# board_exborgs_baru.net
KiCad netlist of a schematic drawn in EAGLE
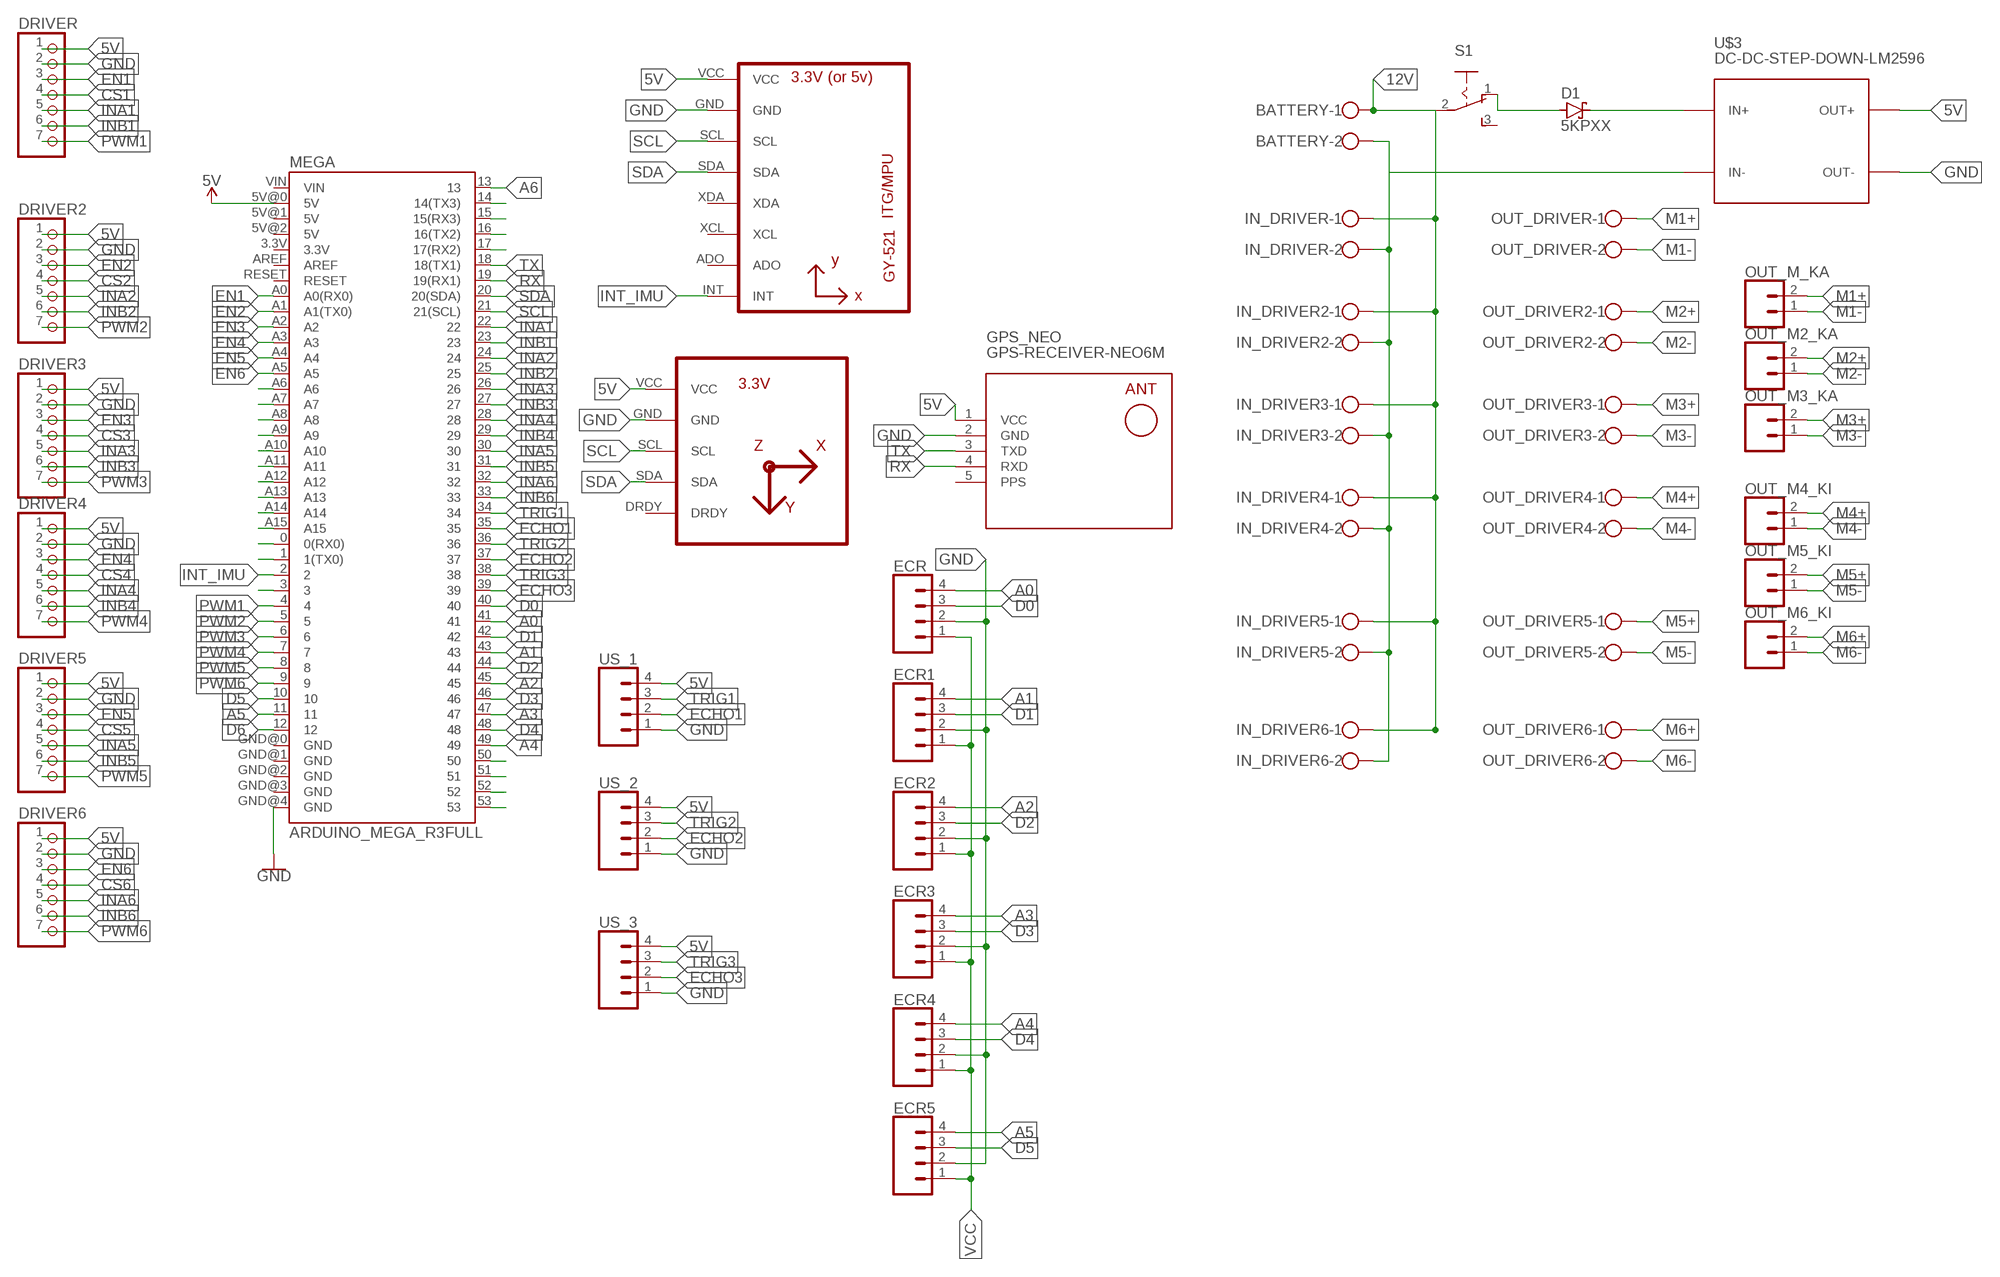
[diagram p0: schematic, sheet 1]

(export (version "E")
  (design (tool "Eeschema 10.0.6"))
  (components
    (comp (ref "BATTERY")
      (value "W237-102")
      (footprint "eagle-import:W237-102")
      (fields (field (name "MPN") "237-102"))
      (libsource (lib "eagle-import") (part "W237-102"))
    )
    (comp (ref "D1")
      (value "5KPXX")
      (footprint "eagle-import:P6T15")
      (libsource (lib "eagle-import") (part "5KPXX"))
    )
    (comp (ref "DRIVER")
      (value "PINHD-1X7")
      (footprint "eagle-import:1X07")
      (libsource (lib "eagle-import") (part "PINHD-1X7"))
    )
    (comp (ref "DRIVER2")
      (value "PINHD-1X7")
      (footprint "eagle-import:1X07")
      (libsource (lib "eagle-import") (part "PINHD-1X7"))
    )
    (comp (ref "DRIVER3")
      (value "PINHD-1X7")
      (footprint "eagle-import:1X07")
      (libsource (lib "eagle-import") (part "PINHD-1X7"))
    )
    (comp (ref "DRIVER4")
      (value "PINHD-1X7")
      (footprint "eagle-import:1X07")
      (libsource (lib "eagle-import") (part "PINHD-1X7"))
    )
    (comp (ref "DRIVER5")
      (value "PINHD-1X7")
      (footprint "eagle-import:1X07")
      (libsource (lib "eagle-import") (part "PINHD-1X7"))
    )
    (comp (ref "DRIVER6")
      (value "PINHD-1X7")
      (footprint "eagle-import:1X07")
      (libsource (lib "eagle-import") (part "PINHD-1X7"))
    )
    (comp (ref "ECR")
      (value "CONN_04POLAR")
      (footprint "eagle-import:MOLEX-1X4")
      (libsource (lib "eagle-import") (part "CONN_04POLAR"))
    )
    (comp (ref "ECR1")
      (value "CONN_04POLAR")
      (footprint "eagle-import:MOLEX-1X4")
      (libsource (lib "eagle-import") (part "CONN_04POLAR"))
    )
    (comp (ref "ECR2")
      (value "CONN_04POLAR")
      (footprint "eagle-import:MOLEX-1X4")
      (libsource (lib "eagle-import") (part "CONN_04POLAR"))
    )
    (comp (ref "ECR3")
      (value "CONN_04POLAR")
      (footprint "eagle-import:MOLEX-1X4")
      (libsource (lib "eagle-import") (part "CONN_04POLAR"))
    )
    (comp (ref "ECR4")
      (value "CONN_04POLAR")
      (footprint "eagle-import:MOLEX-1X4")
      (libsource (lib "eagle-import") (part "CONN_04POLAR"))
    )
    (comp (ref "ECR5")
      (value "CONN_04POLAR")
      (footprint "eagle-import:MOLEX-1X4")
      (libsource (lib "eagle-import") (part "CONN_04POLAR"))
    )
    (comp (ref "GPS_NEO")
      (value "GPS-RECEIVER-NEO6M")
      (footprint "eagle-import:GPS-RECEIVER-NEO6M")
      (libsource (lib "eagle-import") (part "GPS-RECEIVER-NEO6M"))
    )
    (comp (ref "IMU")
      (value "GY-521MPU6050")
      (footprint "eagle-import:GY-521")
      (libsource (lib "eagle-import") (part "GY-521MPU6050"))
    )
    (comp (ref "IN_DRIVER")
      (value "W237-102")
      (footprint "eagle-import:W237-102")
      (fields (field (name "MPN") "237-102"))
      (libsource (lib "eagle-import") (part "W237-102"))
    )
    (comp (ref "IN_DRIVER2")
      (value "W237-102")
      (footprint "eagle-import:W237-102")
      (fields (field (name "MPN") "237-102"))
      (libsource (lib "eagle-import") (part "W237-102"))
    )
    (comp (ref "IN_DRIVER3")
      (value "W237-102")
      (footprint "eagle-import:W237-102")
      (fields (field (name "MPN") "237-102"))
      (libsource (lib "eagle-import") (part "W237-102"))
    )
    (comp (ref "IN_DRIVER4")
      (value "W237-102")
      (footprint "eagle-import:W237-102")
      (fields (field (name "MPN") "237-102"))
      (libsource (lib "eagle-import") (part "W237-102"))
    )
    (comp (ref "IN_DRIVER5")
      (value "W237-102")
      (footprint "eagle-import:W237-102")
      (fields (field (name "MPN") "237-102"))
      (libsource (lib "eagle-import") (part "W237-102"))
    )
    (comp (ref "IN_DRIVER6")
      (value "W237-102")
      (footprint "eagle-import:W237-102")
      (fields (field (name "MPN") "237-102"))
      (libsource (lib "eagle-import") (part "W237-102"))
    )
    (comp (ref "KOMPAS")
      (value "HMC5883LGY-271")
      (footprint "eagle-import:GY-271")
      (libsource (lib "eagle-import") (part "HMC5883LGY-271"))
    )
    (comp (ref "MEGA")
      (value "ARDUINO_MEGA_R3FULL")
      (footprint "eagle-import:ARDUINO_MEGA")
      (libsource (lib "eagle-import") (part "ARDUINO_MEGA_R3FULL"))
    )
    (comp (ref "OUT_DRIVER")
      (value "W237-102")
      (footprint "eagle-import:W237-102")
      (fields (field (name "MPN") "237-102"))
      (libsource (lib "eagle-import") (part "W237-102"))
    )
    (comp (ref "OUT_DRIVER2")
      (value "W237-102")
      (footprint "eagle-import:W237-102")
      (fields (field (name "MPN") "237-102"))
      (libsource (lib "eagle-import") (part "W237-102"))
    )
    (comp (ref "OUT_DRIVER3")
      (value "W237-102")
      (footprint "eagle-import:W237-102")
      (fields (field (name "MPN") "237-102"))
      (libsource (lib "eagle-import") (part "W237-102"))
    )
    (comp (ref "OUT_DRIVER4")
      (value "W237-102")
      (footprint "eagle-import:W237-102")
      (fields (field (name "MPN") "237-102"))
      (libsource (lib "eagle-import") (part "W237-102"))
    )
    (comp (ref "OUT_DRIVER5")
      (value "W237-102")
      (footprint "eagle-import:W237-102")
      (fields (field (name "MPN") "237-102"))
      (libsource (lib "eagle-import") (part "W237-102"))
    )
    (comp (ref "OUT_DRIVER6")
      (value "W237-102")
      (footprint "eagle-import:W237-102")
      (fields (field (name "MPN") "237-102"))
      (libsource (lib "eagle-import") (part "W237-102"))
    )
    (comp (ref "OUT_M2_KA")
      (value "CONN_02POLAR")
      (footprint "eagle-import:MOLEX-1X2")
      (libsource (lib "eagle-import") (part "CONN_02POLAR"))
    )
    (comp (ref "OUT_M3_KA")
      (value "CONN_02POLAR")
      (footprint "eagle-import:MOLEX-1X2")
      (libsource (lib "eagle-import") (part "CONN_02POLAR"))
    )
    (comp (ref "OUT_M4_KI")
      (value "CONN_02POLAR")
      (footprint "eagle-import:MOLEX-1X2")
      (libsource (lib "eagle-import") (part "CONN_02POLAR"))
    )
    (comp (ref "OUT_M5_KI")
      (value "CONN_02POLAR")
      (footprint "eagle-import:MOLEX-1X2")
      (libsource (lib "eagle-import") (part "CONN_02POLAR"))
    )
    (comp (ref "OUT_M6_KI")
      (value "CONN_02POLAR")
      (footprint "eagle-import:MOLEX-1X2")
      (libsource (lib "eagle-import") (part "CONN_02POLAR"))
    )
    (comp (ref "OUT_M_KA")
      (value "CONN_02POLAR")
      (footprint "eagle-import:MOLEX-1X2")
      (libsource (lib "eagle-import") (part "CONN_02POLAR"))
    )
    (comp (ref "S1")
      (value "255SB")
      (footprint "eagle-import:255SB")
      (libsource (lib "eagle-import") (part "255SB"))
    )
    (comp (ref "U$3")
      (value "DC-DC-STEP-DOWN-LM2596")
      (footprint "eagle-import:DC-DC-STEP-DOWN-LM2596")
      (libsource (lib "eagle-import") (part "DC-DC-STEP-DOWN-LM2596"))
    )
    (comp (ref "US_1")
      (value "CONN_04POLAR")
      (footprint "eagle-import:MOLEX-1X4")
      (libsource (lib "eagle-import") (part "CONN_04POLAR"))
    )
    (comp (ref "US_2")
      (value "CONN_04POLAR")
      (footprint "eagle-import:MOLEX-1X4")
      (libsource (lib "eagle-import") (part "CONN_04POLAR"))
    )
    (comp (ref "US_3")
      (value "CONN_04POLAR")
      (footprint "eagle-import:MOLEX-1X4")
      (libsource (lib "eagle-import") (part "CONN_04POLAR"))
    )
  )
  (nets
    (net (code "1") (name "/PPS") (class "Default")
      (node (ref "GPS_NEO") (pin "5") (pinfunction "PPS_5") (pintype "power_in"))
    )
    (net (code "2") (name "5V") (class "Default")
      (node (ref "DRIVER") (pin "1") (pinfunction "1_1") (pintype "passive"))
      (node (ref "DRIVER2") (pin "1") (pinfunction "1_1") (pintype "passive"))
      (node (ref "DRIVER3") (pin "1") (pinfunction "1_1") (pintype "passive"))
      (node (ref "DRIVER4") (pin "1") (pinfunction "1_1") (pintype "passive"))
      (node (ref "DRIVER5") (pin "1") (pinfunction "1_1") (pintype "passive"))
      (node (ref "DRIVER6") (pin "1") (pinfunction "1_1") (pintype "passive"))
      (node (ref "GPS_NEO") (pin "1") (pinfunction "VCC_1") (pintype "bidirectional"))
      (node (ref "IMU") (pin "VCC") (pinfunction "VCC_VCC") (pintype "bidirectional"))
      (node (ref "KOMPAS") (pin "VCC") (pinfunction "VCC_VCC") (pintype "bidirectional"))
      (node (ref "MEGA") (pin "5V@0") (pinfunction "5V_5V@0") (pintype "bidirectional"))
      (node (ref "U$3") (pin "OUT+") (pinfunction "OUT+_OUT+") (pintype "bidirectional"))
      (node (ref "US_1") (pin "4") (pinfunction "4_4") (pintype "passive"))
      (node (ref "US_2") (pin "4") (pinfunction "4_4") (pintype "passive"))
      (node (ref "US_3") (pin "4") (pinfunction "4_4") (pintype "passive"))
    )
    (net (code "3") (name "12V") (class "Default")
      (node (ref "BATTERY") (pin "1") (pinfunction "KL_1") (pintype "passive"))
      (node (ref "IN_DRIVER") (pin "1") (pinfunction "KL_1") (pintype "passive"))
      (node (ref "IN_DRIVER2") (pin "1") (pinfunction "KL_1") (pintype "passive"))
      (node (ref "IN_DRIVER3") (pin "1") (pinfunction "KL_1") (pintype "passive"))
      (node (ref "IN_DRIVER4") (pin "1") (pinfunction "KL_1") (pintype "passive"))
      (node (ref "IN_DRIVER5") (pin "1") (pinfunction "KL_1") (pintype "passive"))
      (node (ref "IN_DRIVER6") (pin "1") (pinfunction "KL_1") (pintype "passive"))
      (node (ref "S1") (pin "2") (pinfunction "P_2") (pintype "passive"))
    )
    (net (code "4") (name "A0") (class "Default")
      (node (ref "ECR") (pin "4") (pinfunction "4_4") (pintype "passive"))
      (node (ref "MEGA") (pin "41") (pinfunction "41_41") (pintype "bidirectional"))
    )
    (net (code "5") (name "A1") (class "Default")
      (node (ref "ECR1") (pin "4") (pinfunction "4_4") (pintype "passive"))
      (node (ref "MEGA") (pin "43") (pinfunction "43_43") (pintype "bidirectional"))
    )
    (net (code "6") (name "A2") (class "Default")
      (node (ref "ECR2") (pin "4") (pinfunction "4_4") (pintype "passive"))
      (node (ref "MEGA") (pin "45") (pinfunction "45_45") (pintype "bidirectional"))
    )
    (net (code "7") (name "A3") (class "Default")
      (node (ref "ECR3") (pin "4") (pinfunction "4_4") (pintype "passive"))
      (node (ref "MEGA") (pin "47") (pinfunction "47_47") (pintype "bidirectional"))
    )
    (net (code "8") (name "A4") (class "Default")
      (node (ref "ECR4") (pin "4") (pinfunction "4_4") (pintype "passive"))
      (node (ref "MEGA") (pin "49") (pinfunction "49_49") (pintype "bidirectional"))
    )
    (net (code "9") (name "A5") (class "Default")
      (node (ref "ECR5") (pin "4") (pinfunction "4_4") (pintype "passive"))
      (node (ref "MEGA") (pin "11") (pinfunction "11_11") (pintype "bidirectional"))
    )
    (net (code "10") (name "A6") (class "Default")
      (node (ref "MEGA") (pin "13") (pinfunction "13_13") (pintype "bidirectional"))
    )
    (net (code "11") (name "CS1") (class "Default")
      (node (ref "DRIVER") (pin "4") (pinfunction "4_4") (pintype "passive"))
    )
    (net (code "12") (name "CS2") (class "Default")
      (node (ref "DRIVER2") (pin "4") (pinfunction "4_4") (pintype "passive"))
    )
    (net (code "13") (name "CS3") (class "Default")
      (node (ref "DRIVER3") (pin "4") (pinfunction "4_4") (pintype "passive"))
    )
    (net (code "14") (name "CS4") (class "Default")
      (node (ref "DRIVER4") (pin "4") (pinfunction "4_4") (pintype "passive"))
    )
    (net (code "15") (name "CS5") (class "Default")
      (node (ref "DRIVER5") (pin "4") (pinfunction "4_4") (pintype "passive"))
    )
    (net (code "16") (name "CS6") (class "Default")
      (node (ref "DRIVER6") (pin "4") (pinfunction "4_4") (pintype "passive"))
    )
    (net (code "17") (name "D0") (class "Default")
      (node (ref "ECR") (pin "3") (pinfunction "3_3") (pintype "passive"))
      (node (ref "MEGA") (pin "40") (pinfunction "40_40") (pintype "bidirectional"))
    )
    (net (code "18") (name "D1") (class "Default")
      (node (ref "ECR1") (pin "3") (pinfunction "3_3") (pintype "passive"))
      (node (ref "MEGA") (pin "42") (pinfunction "42_42") (pintype "bidirectional"))
    )
    (net (code "19") (name "D2") (class "Default")
      (node (ref "ECR2") (pin "3") (pinfunction "3_3") (pintype "passive"))
      (node (ref "MEGA") (pin "44") (pinfunction "44_44") (pintype "bidirectional"))
    )
    (net (code "20") (name "D3") (class "Default")
      (node (ref "ECR3") (pin "3") (pinfunction "3_3") (pintype "passive"))
      (node (ref "MEGA") (pin "46") (pinfunction "46_46") (pintype "bidirectional"))
    )
    (net (code "21") (name "D4") (class "Default")
      (node (ref "ECR4") (pin "3") (pinfunction "3_3") (pintype "passive"))
      (node (ref "MEGA") (pin "48") (pinfunction "48_48") (pintype "bidirectional"))
    )
    (net (code "22") (name "D5") (class "Default")
      (node (ref "ECR5") (pin "3") (pinfunction "3_3") (pintype "passive"))
      (node (ref "MEGA") (pin "10") (pinfunction "10_10") (pintype "bidirectional"))
    )
    (net (code "23") (name "D6") (class "Default")
      (node (ref "MEGA") (pin "12") (pinfunction "12_12") (pintype "bidirectional"))
    )
    (net (code "24") (name "ECHO1") (class "Default")
      (node (ref "MEGA") (pin "35") (pinfunction "35_35") (pintype "bidirectional"))
      (node (ref "US_1") (pin "2") (pinfunction "2_2") (pintype "passive"))
    )
    (net (code "25") (name "ECHO2") (class "Default")
      (node (ref "MEGA") (pin "37") (pinfunction "37_37") (pintype "bidirectional"))
      (node (ref "US_2") (pin "2") (pinfunction "2_2") (pintype "passive"))
    )
    (net (code "26") (name "ECHO3") (class "Default")
      (node (ref "MEGA") (pin "39") (pinfunction "39_39") (pintype "bidirectional"))
      (node (ref "US_3") (pin "2") (pinfunction "2_2") (pintype "passive"))
    )
    (net (code "27") (name "EN1") (class "Default")
      (node (ref "DRIVER") (pin "3") (pinfunction "3_3") (pintype "passive"))
      (node (ref "MEGA") (pin "A0") (pinfunction "A0(RX0)_A0") (pintype "bidirectional"))
    )
    (net (code "28") (name "EN2") (class "Default")
      (node (ref "DRIVER2") (pin "3") (pinfunction "3_3") (pintype "passive"))
      (node (ref "MEGA") (pin "A1") (pinfunction "A1(TX0)_A1") (pintype "bidirectional"))
    )
    (net (code "29") (name "EN3") (class "Default")
      (node (ref "DRIVER3") (pin "3") (pinfunction "3_3") (pintype "passive"))
      (node (ref "MEGA") (pin "A2") (pinfunction "A2_A2") (pintype "bidirectional"))
    )
    (net (code "30") (name "EN4") (class "Default")
      (node (ref "DRIVER4") (pin "3") (pinfunction "3_3") (pintype "passive"))
      (node (ref "MEGA") (pin "A3") (pinfunction "A3_A3") (pintype "bidirectional"))
    )
    (net (code "31") (name "EN5") (class "Default")
      (node (ref "DRIVER5") (pin "3") (pinfunction "3_3") (pintype "passive"))
      (node (ref "MEGA") (pin "A4") (pinfunction "A4_A4") (pintype "bidirectional"))
    )
    (net (code "32") (name "EN6") (class "Default")
      (node (ref "DRIVER6") (pin "3") (pinfunction "3_3") (pintype "passive"))
      (node (ref "MEGA") (pin "A5") (pinfunction "A5_A5") (pintype "bidirectional"))
    )
    (net (code "33") (name "GND") (class "Default")
      (node (ref "DRIVER") (pin "2") (pinfunction "2_2") (pintype "passive"))
      (node (ref "DRIVER2") (pin "2") (pinfunction "2_2") (pintype "passive"))
      (node (ref "DRIVER3") (pin "2") (pinfunction "2_2") (pintype "passive"))
      (node (ref "DRIVER4") (pin "2") (pinfunction "2_2") (pintype "passive"))
      (node (ref "DRIVER5") (pin "2") (pinfunction "2_2") (pintype "passive"))
      (node (ref "DRIVER6") (pin "2") (pinfunction "2_2") (pintype "passive"))
      (node (ref "ECR") (pin "2") (pinfunction "2_2") (pintype "passive"))
      (node (ref "ECR1") (pin "2") (pinfunction "2_2") (pintype "passive"))
      (node (ref "ECR2") (pin "2") (pinfunction "2_2") (pintype "passive"))
      (node (ref "ECR3") (pin "2") (pinfunction "2_2") (pintype "passive"))
      (node (ref "ECR4") (pin "2") (pinfunction "2_2") (pintype "passive"))
      (node (ref "ECR5") (pin "2") (pinfunction "2_2") (pintype "passive"))
      (node (ref "GPS_NEO") (pin "2") (pinfunction "GND_2") (pintype "bidirectional"))
      (node (ref "IMU") (pin "GND") (pinfunction "GND_GND") (pintype "bidirectional"))
      (node (ref "KOMPAS") (pin "GND") (pinfunction "GND_GND") (pintype "bidirectional"))
      (node (ref "MEGA") (pin "GND@4") (pinfunction "GND_GND@4") (pintype "bidirectional"))
      (node (ref "U$3") (pin "OUT-") (pinfunction "OUT-_OUT-") (pintype "bidirectional"))
      (node (ref "US_1") (pin "1") (pinfunction "1_1") (pintype "passive"))
      (node (ref "US_2") (pin "1") (pinfunction "1_1") (pintype "passive"))
      (node (ref "US_3") (pin "1") (pinfunction "1_1") (pintype "passive"))
    )
    (net (code "34") (name "INA1") (class "Default")
      (node (ref "DRIVER") (pin "5") (pinfunction "5_5") (pintype "passive"))
      (node (ref "MEGA") (pin "22") (pinfunction "22_22") (pintype "bidirectional"))
    )
    (net (code "35") (name "INA2") (class "Default")
      (node (ref "DRIVER2") (pin "5") (pinfunction "5_5") (pintype "passive"))
      (node (ref "MEGA") (pin "24") (pinfunction "24_24") (pintype "bidirectional"))
    )
    (net (code "36") (name "INA3") (class "Default")
      (node (ref "DRIVER3") (pin "5") (pinfunction "5_5") (pintype "passive"))
      (node (ref "MEGA") (pin "26") (pinfunction "26_26") (pintype "bidirectional"))
    )
    (net (code "37") (name "INA4") (class "Default")
      (node (ref "DRIVER4") (pin "5") (pinfunction "5_5") (pintype "passive"))
      (node (ref "MEGA") (pin "28") (pinfunction "28_28") (pintype "bidirectional"))
    )
    (net (code "38") (name "INA5") (class "Default")
      (node (ref "DRIVER5") (pin "5") (pinfunction "5_5") (pintype "passive"))
      (node (ref "MEGA") (pin "30") (pinfunction "30_30") (pintype "bidirectional"))
    )
    (net (code "39") (name "INA6") (class "Default")
      (node (ref "DRIVER6") (pin "5") (pinfunction "5_5") (pintype "passive"))
      (node (ref "MEGA") (pin "32") (pinfunction "32_32") (pintype "bidirectional"))
    )
    (net (code "40") (name "INB1") (class "Default")
      (node (ref "DRIVER") (pin "6") (pinfunction "6_6") (pintype "passive"))
      (node (ref "MEGA") (pin "23") (pinfunction "23_23") (pintype "bidirectional"))
    )
    (net (code "41") (name "INB2") (class "Default")
      (node (ref "DRIVER2") (pin "6") (pinfunction "6_6") (pintype "passive"))
      (node (ref "MEGA") (pin "25") (pinfunction "25_25") (pintype "bidirectional"))
    )
    (net (code "42") (name "INB3") (class "Default")
      (node (ref "DRIVER3") (pin "6") (pinfunction "6_6") (pintype "passive"))
      (node (ref "MEGA") (pin "27") (pinfunction "27_27") (pintype "bidirectional"))
    )
    (net (code "43") (name "INB4") (class "Default")
      (node (ref "DRIVER4") (pin "6") (pinfunction "6_6") (pintype "passive"))
      (node (ref "MEGA") (pin "29") (pinfunction "29_29") (pintype "bidirectional"))
    )
    (net (code "44") (name "INB5") (class "Default")
      (node (ref "DRIVER5") (pin "6") (pinfunction "6_6") (pintype "passive"))
      (node (ref "MEGA") (pin "31") (pinfunction "31_31") (pintype "bidirectional"))
    )
    (net (code "45") (name "INB6") (class "Default")
      (node (ref "DRIVER6") (pin "6") (pinfunction "6_6") (pintype "passive"))
      (node (ref "MEGA") (pin "33") (pinfunction "33_33") (pintype "bidirectional"))
    )
    (net (code "46") (name "INT_IMU") (class "Default")
      (node (ref "IMU") (pin "INT") (pinfunction "INT_INT") (pintype "bidirectional"))
      (node (ref "MEGA") (pin "2") (pinfunction "2_2") (pintype "bidirectional"))
    )
    (net (code "47") (name "M1+") (class "Default")
      (node (ref "OUT_DRIVER") (pin "1") (pinfunction "KL_1") (pintype "passive"))
      (node (ref "OUT_M_KA") (pin "2") (pinfunction "2_2") (pintype "passive"))
    )
    (net (code "48") (name "M1-") (class "Default")
      (node (ref "OUT_DRIVER") (pin "2") (pinfunction "KL_2") (pintype "passive"))
      (node (ref "OUT_M_KA") (pin "1") (pinfunction "1_1") (pintype "passive"))
    )
    (net (code "49") (name "M2+") (class "Default")
      (node (ref "OUT_DRIVER2") (pin "1") (pinfunction "KL_1") (pintype "passive"))
      (node (ref "OUT_M2_KA") (pin "2") (pinfunction "2_2") (pintype "passive"))
    )
    (net (code "50") (name "M2-") (class "Default")
      (node (ref "OUT_DRIVER2") (pin "2") (pinfunction "KL_2") (pintype "passive"))
      (node (ref "OUT_M2_KA") (pin "1") (pinfunction "1_1") (pintype "passive"))
    )
    (net (code "51") (name "M3+") (class "Default")
      (node (ref "OUT_DRIVER3") (pin "1") (pinfunction "KL_1") (pintype "passive"))
      (node (ref "OUT_M3_KA") (pin "2") (pinfunction "2_2") (pintype "passive"))
    )
    (net (code "52") (name "M3-") (class "Default")
      (node (ref "OUT_DRIVER3") (pin "2") (pinfunction "KL_2") (pintype "passive"))
      (node (ref "OUT_M3_KA") (pin "1") (pinfunction "1_1") (pintype "passive"))
    )
    (net (code "53") (name "M4+") (class "Default")
      (node (ref "OUT_DRIVER4") (pin "1") (pinfunction "KL_1") (pintype "passive"))
      (node (ref "OUT_M4_KI") (pin "2") (pinfunction "2_2") (pintype "passive"))
    )
    (net (code "54") (name "M4-") (class "Default")
      (node (ref "OUT_DRIVER4") (pin "2") (pinfunction "KL_2") (pintype "passive"))
      (node (ref "OUT_M4_KI") (pin "1") (pinfunction "1_1") (pintype "passive"))
    )
    (net (code "55") (name "M5+") (class "Default")
      (node (ref "OUT_DRIVER5") (pin "1") (pinfunction "KL_1") (pintype "passive"))
      (node (ref "OUT_M5_KI") (pin "2") (pinfunction "2_2") (pintype "passive"))
    )
    (net (code "56") (name "M5-") (class "Default")
      (node (ref "OUT_DRIVER5") (pin "2") (pinfunction "KL_2") (pintype "passive"))
      (node (ref "OUT_M5_KI") (pin "1") (pinfunction "1_1") (pintype "passive"))
    )
    (net (code "57") (name "M6+") (class "Default")
      (node (ref "OUT_DRIVER6") (pin "1") (pinfunction "KL_1") (pintype "passive"))
      (node (ref "OUT_M6_KI") (pin "2") (pinfunction "2_2") (pintype "passive"))
    )
    (net (code "58") (name "M6-") (class "Default")
      (node (ref "OUT_DRIVER6") (pin "2") (pinfunction "KL_2") (pintype "passive"))
      (node (ref "OUT_M6_KI") (pin "1") (pinfunction "1_1") (pintype "passive"))
    )
    (net (code "59") (name "Net-(BATTERYB-KL)") (class "Default")
      (node (ref "BATTERY") (pin "2") (pinfunction "KL_2") (pintype "passive"))
      (node (ref "IN_DRIVER") (pin "2") (pinfunction "KL_2") (pintype "passive"))
      (node (ref "IN_DRIVER2") (pin "2") (pinfunction "KL_2") (pintype "passive"))
      (node (ref "IN_DRIVER3") (pin "2") (pinfunction "KL_2") (pintype "passive"))
      (node (ref "IN_DRIVER4") (pin "2") (pinfunction "KL_2") (pintype "passive"))
      (node (ref "IN_DRIVER5") (pin "2") (pinfunction "KL_2") (pintype "passive"))
      (node (ref "IN_DRIVER6") (pin "2") (pinfunction "KL_2") (pintype "passive"))
      (node (ref "U$3") (pin "IN-") (pinfunction "IN-_IN-") (pintype "bidirectional"))
    )
    (net (code "60") (name "Net-(D1-PadC)") (class "Default")
      (node (ref "D1") (pin "C") (pinfunction "C_C") (pintype "passive"))
      (node (ref "U$3") (pin "IN+") (pinfunction "IN+_IN+") (pintype "bidirectional"))
    )
    (net (code "61") (name "Net-(S1-O)") (class "Default")
      (node (ref "D1") (pin "A") (pinfunction "A_A") (pintype "passive"))
      (node (ref "S1") (pin "1") (pinfunction "O_1") (pintype "passive"))
    )
    (net (code "62") (name "PWM1") (class "Default")
      (node (ref "DRIVER") (pin "7") (pinfunction "7_7") (pintype "passive"))
      (node (ref "MEGA") (pin "4") (pinfunction "4_4") (pintype "bidirectional"))
    )
    (net (code "63") (name "PWM2") (class "Default")
      (node (ref "DRIVER2") (pin "7") (pinfunction "7_7") (pintype "passive"))
      (node (ref "MEGA") (pin "5") (pinfunction "5_5") (pintype "bidirectional"))
    )
    (net (code "64") (name "PWM3") (class "Default")
      (node (ref "DRIVER3") (pin "7") (pinfunction "7_7") (pintype "passive"))
      (node (ref "MEGA") (pin "6") (pinfunction "6_6") (pintype "bidirectional"))
    )
    (net (code "65") (name "PWM4") (class "Default")
      (node (ref "DRIVER4") (pin "7") (pinfunction "7_7") (pintype "passive"))
      (node (ref "MEGA") (pin "7") (pinfunction "7_7") (pintype "bidirectional"))
    )
    (net (code "66") (name "PWM5") (class "Default")
      (node (ref "DRIVER5") (pin "7") (pinfunction "7_7") (pintype "passive"))
      (node (ref "MEGA") (pin "8") (pinfunction "8_8") (pintype "bidirectional"))
    )
    (net (code "67") (name "PWM6") (class "Default")
      (node (ref "DRIVER6") (pin "7") (pinfunction "7_7") (pintype "passive"))
      (node (ref "MEGA") (pin "9") (pinfunction "9_9") (pintype "bidirectional"))
    )
    (net (code "68") (name "RX") (class "Default")
      (node (ref "GPS_NEO") (pin "4") (pinfunction "RXD_4") (pintype "power_in"))
      (node (ref "MEGA") (pin "19") (pinfunction "19(RX1)_19") (pintype "bidirectional"))
    )
    (net (code "69") (name "SCL") (class "Default")
      (node (ref "IMU") (pin "SCL") (pinfunction "SCL_SCL") (pintype "bidirectional"))
      (node (ref "KOMPAS") (pin "SCL") (pinfunction "SCL_SCL") (pintype "bidirectional"))
      (node (ref "MEGA") (pin "21") (pinfunction "21(SCL)_21") (pintype "bidirectional"))
    )
    (net (code "70") (name "SDA") (class "Default")
      (node (ref "IMU") (pin "SDA") (pinfunction "SDA_SDA") (pintype "bidirectional"))
      (node (ref "KOMPAS") (pin "SDA") (pinfunction "SDA_SDA") (pintype "bidirectional"))
      (node (ref "MEGA") (pin "20") (pinfunction "20(SDA)_20") (pintype "bidirectional"))
    )
    (net (code "71") (name "TRIG1") (class "Default")
      (node (ref "MEGA") (pin "34") (pinfunction "34_34") (pintype "bidirectional"))
      (node (ref "US_1") (pin "3") (pinfunction "3_3") (pintype "passive"))
    )
    (net (code "72") (name "TRIG2") (class "Default")
      (node (ref "MEGA") (pin "36") (pinfunction "36_36") (pintype "bidirectional"))
      (node (ref "US_2") (pin "3") (pinfunction "3_3") (pintype "passive"))
    )
    (net (code "73") (name "TRIG3") (class "Default")
      (node (ref "MEGA") (pin "38") (pinfunction "38_38") (pintype "bidirectional"))
      (node (ref "US_3") (pin "3") (pinfunction "3_3") (pintype "passive"))
    )
    (net (code "74") (name "TX") (class "Default")
      (node (ref "GPS_NEO") (pin "3") (pinfunction "TXD_3") (pintype "bidirectional"))
      (node (ref "MEGA") (pin "18") (pinfunction "18(TX1)_18") (pintype "bidirectional"))
    )
    (net (code "75") (name "VCC") (class "Default")
      (node (ref "ECR") (pin "1") (pinfunction "1_1") (pintype "passive"))
      (node (ref "ECR1") (pin "1") (pinfunction "1_1") (pintype "passive"))
      (node (ref "ECR2") (pin "1") (pinfunction "1_1") (pintype "passive"))
      (node (ref "ECR3") (pin "1") (pinfunction "1_1") (pintype "passive"))
      (node (ref "ECR4") (pin "1") (pinfunction "1_1") (pintype "passive"))
      (node (ref "ECR5") (pin "1") (pinfunction "1_1") (pintype "passive"))
    )
    (net (code "76") (name "unconnected-(IMU-PadADO)") (class "Default")
      (node (ref "IMU") (pin "ADO") (pinfunction "ADO_ADO") (pintype "bidirectional"))
    )
    (net (code "77") (name "unconnected-(IMU-PadXCL)") (class "Default")
      (node (ref "IMU") (pin "XCL") (pinfunction "XCL_XCL") (pintype "bidirectional"))
    )
    (net (code "78") (name "unconnected-(IMU-PadXDA)") (class "Default")
      (node (ref "IMU") (pin "XDA") (pinfunction "XDA_XDA") (pintype "bidirectional"))
    )
    (net (code "79") (name "unconnected-(KOMPAS-PadDRDY)") (class "Default")
      (node (ref "KOMPAS") (pin "DRDY") (pinfunction "DRDY_DRDY") (pintype "bidirectional"))
    )
    (net (code "80") (name "unconnected-(MEGA-0(RX0)-Pad0)") (class "Default")
      (node (ref "MEGA") (pin "0") (pinfunction "0(RX0)_0") (pintype "bidirectional"))
    )
    (net (code "81") (name "unconnected-(MEGA-1(TX0)-Pad1)") (class "Default")
      (node (ref "MEGA") (pin "1") (pinfunction "1(TX0)_1") (pintype "bidirectional"))
    )
    (net (code "82") (name "unconnected-(MEGA-5V-Pad5V@1)") (class "Default")
      (node (ref "MEGA") (pin "5V@1") (pinfunction "5V_5V@1") (pintype "bidirectional"))
    )
    (net (code "83") (name "unconnected-(MEGA-5V-Pad5V@2)") (class "Default")
      (node (ref "MEGA") (pin "5V@2") (pinfunction "5V_5V@2") (pintype "bidirectional"))
    )
    (net (code "84") (name "unconnected-(MEGA-14(TX3)-Pad14)") (class "Default")
      (node (ref "MEGA") (pin "14") (pinfunction "14(TX3)_14") (pintype "bidirectional"))
    )
    (net (code "85") (name "unconnected-(MEGA-15(RX3)-Pad15)") (class "Default")
      (node (ref "MEGA") (pin "15") (pinfunction "15(RX3)_15") (pintype "bidirectional"))
    )
    (net (code "86") (name "unconnected-(MEGA-16(TX2)-Pad16)") (class "Default")
      (node (ref "MEGA") (pin "16") (pinfunction "16(TX2)_16") (pintype "bidirectional"))
    )
    (net (code "87") (name "unconnected-(MEGA-17(RX2)-Pad17)") (class "Default")
      (node (ref "MEGA") (pin "17") (pinfunction "17(RX2)_17") (pintype "bidirectional"))
    )
    (net (code "88") (name "unconnected-(MEGA-GND-PadGND@0)") (class "Default")
      (node (ref "MEGA") (pin "GND@0") (pinfunction "GND_GND@0") (pintype "bidirectional"))
    )
    (net (code "89") (name "unconnected-(MEGA-GND-PadGND@1)") (class "Default")
      (node (ref "MEGA") (pin "GND@1") (pinfunction "GND_GND@1") (pintype "bidirectional"))
    )
    (net (code "90") (name "unconnected-(MEGA-GND-PadGND@2)") (class "Default")
      (node (ref "MEGA") (pin "GND@2") (pinfunction "GND_GND@2") (pintype "bidirectional"))
    )
    (net (code "91") (name "unconnected-(MEGA-GND-PadGND@3)") (class "Default")
      (node (ref "MEGA") (pin "GND@3") (pinfunction "GND_GND@3") (pintype "bidirectional"))
    )
    (net (code "92") (name "unconnected-(MEGA-Pad3)") (class "Default")
      (node (ref "MEGA") (pin "3") (pinfunction "3_3") (pintype "bidirectional"))
    )
    (net (code "93") (name "unconnected-(MEGA-Pad3.3V)") (class "Default")
      (node (ref "MEGA") (pin "3.3V") (pinfunction "3.3V_3.3V") (pintype "bidirectional"))
    )
    (net (code "94") (name "unconnected-(MEGA-Pad50)") (class "Default")
      (node (ref "MEGA") (pin "50") (pinfunction "50_50") (pintype "bidirectional"))
    )
    (net (code "95") (name "unconnected-(MEGA-Pad51)") (class "Default")
      (node (ref "MEGA") (pin "51") (pinfunction "51_51") (pintype "bidirectional"))
    )
    (net (code "96") (name "unconnected-(MEGA-Pad52)") (class "Default")
      (node (ref "MEGA") (pin "52") (pinfunction "52_52") (pintype "bidirectional"))
    )
    (net (code "97") (name "unconnected-(MEGA-Pad53)") (class "Default")
      (node (ref "MEGA") (pin "53") (pinfunction "53_53") (pintype "bidirectional"))
    )
    (net (code "98") (name "unconnected-(MEGA-PadA6)") (class "Default")
      (node (ref "MEGA") (pin "A6") (pinfunction "A6_A6") (pintype "bidirectional"))
    )
    (net (code "99") (name "unconnected-(MEGA-PadA7)") (class "Default")
      (node (ref "MEGA") (pin "A7") (pinfunction "A7_A7") (pintype "bidirectional"))
    )
    (net (code "100") (name "unconnected-(MEGA-PadA8)") (class "Default")
      (node (ref "MEGA") (pin "A8") (pinfunction "A8_A8") (pintype "bidirectional"))
    )
    (net (code "101") (name "unconnected-(MEGA-PadA9)") (class "Default")
      (node (ref "MEGA") (pin "A9") (pinfunction "A9_A9") (pintype "bidirectional"))
    )
    (net (code "102") (name "unconnected-(MEGA-PadA10)") (class "Default")
      (node (ref "MEGA") (pin "A10") (pinfunction "A10_A10") (pintype "bidirectional"))
    )
    (net (code "103") (name "unconnected-(MEGA-PadA11)") (class "Default")
      (node (ref "MEGA") (pin "A11") (pinfunction "A11_A11") (pintype "bidirectional"))
    )
    (net (code "104") (name "unconnected-(MEGA-PadA12)") (class "Default")
      (node (ref "MEGA") (pin "A12") (pinfunction "A12_A12") (pintype "bidirectional"))
    )
    (net (code "105") (name "unconnected-(MEGA-PadA13)") (class "Default")
      (node (ref "MEGA") (pin "A13") (pinfunction "A13_A13") (pintype "bidirectional"))
    )
    (net (code "106") (name "unconnected-(MEGA-PadA14)") (class "Default")
      (node (ref "MEGA") (pin "A14") (pinfunction "A14_A14") (pintype "bidirectional"))
    )
    (net (code "107") (name "unconnected-(MEGA-PadA15)") (class "Default")
      (node (ref "MEGA") (pin "A15") (pinfunction "A15_A15") (pintype "bidirectional"))
    )
    (net (code "108") (name "unconnected-(MEGA-PadAREF)") (class "Default")
      (node (ref "MEGA") (pin "AREF") (pinfunction "AREF_AREF") (pintype "bidirectional"))
    )
    (net (code "109") (name "unconnected-(MEGA-PadRESET)") (class "Default")
      (node (ref "MEGA") (pin "RESET") (pinfunction "RESET_RESET") (pintype "bidirectional"))
    )
    (net (code "110") (name "unconnected-(MEGA-PadVIN)") (class "Default")
      (node (ref "MEGA") (pin "VIN") (pinfunction "VIN_VIN") (pintype "bidirectional"))
    )
    (net (code "111") (name "unconnected-(S1-S-Pad3)") (class "Default")
      (node (ref "S1") (pin "3") (pinfunction "S_3") (pintype "passive"))
    )
  )
)
